# ethero_v1.net
KiCad netlist of a schematic drawn in EAGLE
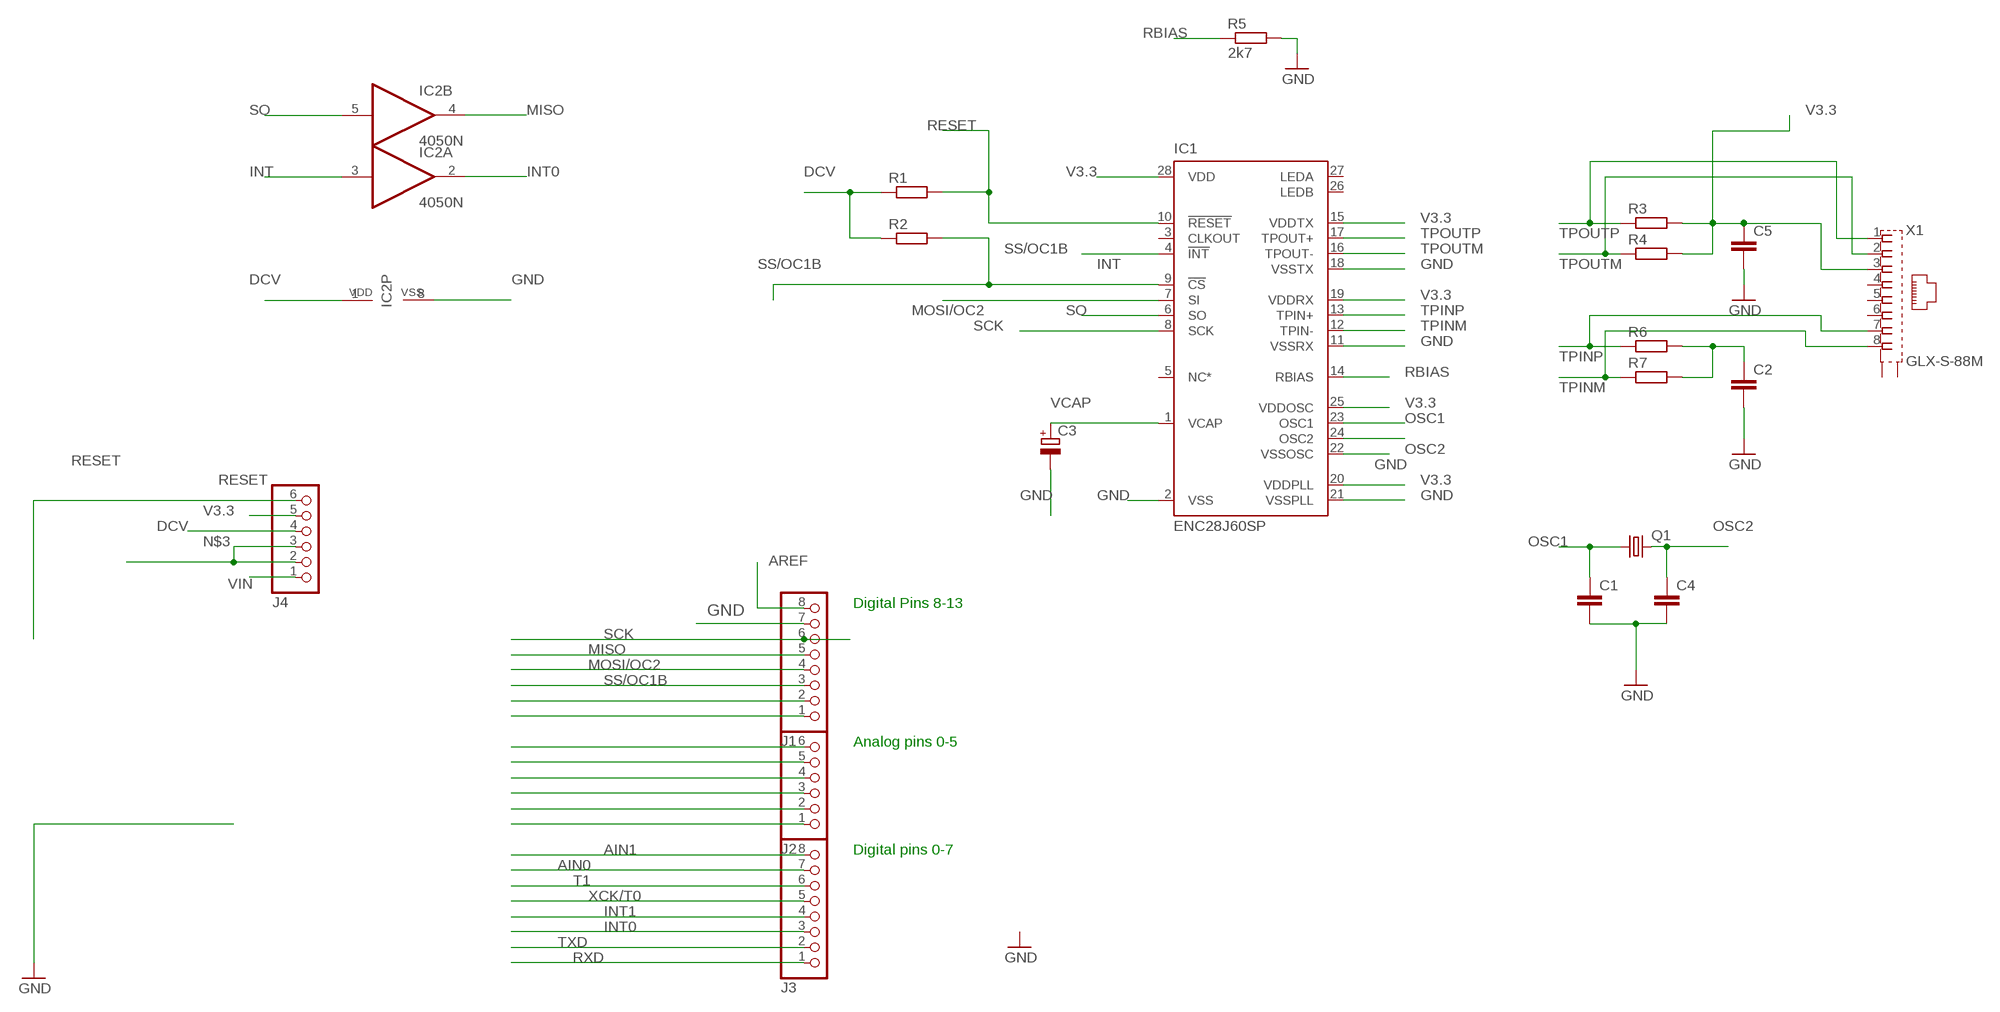
[diagram p0: schematic, sheet 1]

(export (version "E")
  (design (tool "Eeschema 10.0.6"))
  (components
    (comp (ref "C1")
      (value "C-EU025-025X050")
      (footprint "eagle-import:C025-025X050")
      (libsource (lib "eagle-import") (part "C-EU025-025X050"))
    )
    (comp (ref "C2")
      (value "C-EU025-025X050")
      (footprint "eagle-import:C025-025X050")
      (libsource (lib "eagle-import") (part "C-EU025-025X050"))
    )
    (comp (ref "C3")
      (value "CPOL-EUE5-5")
      (footprint "eagle-import:E5-5")
      (libsource (lib "eagle-import") (part "CPOL-EUE5-5"))
    )
    (comp (ref "C4")
      (value "C-EU025-025X050")
      (footprint "eagle-import:C025-025X050")
      (libsource (lib "eagle-import") (part "C-EU025-025X050"))
    )
    (comp (ref "C5")
      (value "C-EU025-025X050")
      (footprint "eagle-import:C025-025X050")
      (libsource (lib "eagle-import") (part "C-EU025-025X050"))
    )
    (comp (ref "IC1")
      (value "ENC28J60SP")
      (footprint "eagle-import:DIL28-3")
      (fields (field (name "MF") "MICROCHIP") (field (name "MPN") "ENC28J60/SP"))
      (libsource (lib "eagle-import") (part "ENC28J60SP"))
    )
    (comp (ref "IC2")
      (value "4050N")
      (footprint "eagle-import:DIL16")
      (libsource (lib "eagle-import") (part "4050N"))
    )
    (comp (ref "J1")
      (value "PINHD-1X8")
      (footprint "eagle-import:1X08")
      (libsource (lib "eagle-import") (part "PINHD-1X8"))
    )
    (comp (ref "J2")
      (value "PINHD-1X6")
      (footprint "eagle-import:1X06")
      (libsource (lib "eagle-import") (part "PINHD-1X6"))
    )
    (comp (ref "J3")
      (value "PINHD-1X8")
      (footprint "eagle-import:1X08")
      (libsource (lib "eagle-import") (part "PINHD-1X8"))
    )
    (comp (ref "J4")
      (value "PINHD-1X6")
      (footprint "eagle-import:1X06")
      (libsource (lib "eagle-import") (part "PINHD-1X6"))
    )
    (comp (ref "Q1")
      (value "CRYSTALHC18U-V")
      (footprint "eagle-import:HC18U-V")
      (libsource (lib "eagle-import") (part "CRYSTALHC18U-V"))
    )
    (comp (ref "R1")
      (value "R-EU_0204/7")
      (footprint "eagle-import:0204_7")
      (libsource (lib "eagle-import") (part "R-EU_0204/7"))
    )
    (comp (ref "R2")
      (value "R-EU_0204/7")
      (footprint "eagle-import:0204_7")
      (libsource (lib "eagle-import") (part "R-EU_0204/7"))
    )
    (comp (ref "R3")
      (value "R-EU_0204/7")
      (footprint "eagle-import:0204_7")
      (libsource (lib "eagle-import") (part "R-EU_0204/7"))
    )
    (comp (ref "R4")
      (value "R-EU_0204/7")
      (footprint "eagle-import:0204_7")
      (libsource (lib "eagle-import") (part "R-EU_0204/7"))
    )
    (comp (ref "R5")
      (value "2k7")
      (footprint "eagle-import:0204_7")
      (libsource (lib "eagle-import") (part "R-EU_0204/7"))
    )
    (comp (ref "R6")
      (value "R-EU_0204/7")
      (footprint "eagle-import:0204_7")
      (libsource (lib "eagle-import") (part "R-EU_0204/7"))
    )
    (comp (ref "R7")
      (value "R-EU_0204/7")
      (footprint "eagle-import:0204_7")
      (libsource (lib "eagle-import") (part "R-EU_0204/7"))
    )
    (comp (ref "X1")
      (value "GLX-S-88M")
      (footprint "eagle-import:GLX-S-88M")
      (libsource (lib "eagle-import") (part "GLX-S-88M"))
    )
  )
  (nets
    (net (code "1") (name "/AIN0") (class "Default")
      (node (ref "J3") (pin "7") (pinfunction "7_7") (pintype "passive"))
    )
    (net (code "2") (name "/AIN1") (class "Default")
      (node (ref "J3") (pin "8") (pinfunction "8_8") (pintype "passive"))
    )
    (net (code "3") (name "/AREF") (class "Default")
      (node (ref "J1") (pin "8") (pinfunction "8_8") (pintype "passive"))
    )
    (net (code "4") (name "/DCV") (class "Default")
      (node (ref "IC2") (pin "1") (pinfunction "VDD_1") (pintype "power_in"))
      (node (ref "J4") (pin "4") (pinfunction "4_4") (pintype "passive"))
      (node (ref "R1") (pin "1") (pinfunction "1_1") (pintype "passive"))
      (node (ref "R2") (pin "1") (pinfunction "1_1") (pintype "passive"))
    )
    (net (code "5") (name "/INT") (class "Default")
      (node (ref "IC1") (pin "4") (pinfunction "~{INT}_4") (pintype "output"))
      (node (ref "IC2") (pin "3") (pinfunction "I_3") (pintype "input"))
    )
    (net (code "6") (name "/INT0") (class "Default")
      (node (ref "IC2") (pin "2") (pinfunction "O_2") (pintype "output"))
      (node (ref "J3") (pin "3") (pinfunction "3_3") (pintype "passive"))
    )
    (net (code "7") (name "/INT1") (class "Default")
      (node (ref "J3") (pin "4") (pinfunction "4_4") (pintype "passive"))
    )
    (net (code "8") (name "/MISO") (class "Default")
      (node (ref "IC2") (pin "4") (pinfunction "O_4") (pintype "output"))
      (node (ref "J1") (pin "5") (pinfunction "5_5") (pintype "passive"))
    )
    (net (code "9") (name "/MOSI{slash}OC2") (class "Default")
      (node (ref "IC1") (pin "7") (pinfunction "SI_7") (pintype "input"))
      (node (ref "J1") (pin "4") (pinfunction "4_4") (pintype "passive"))
    )
    (net (code "10") (name "/N$3") (class "Default")
      (node (ref "J4") (pin "2") (pinfunction "2_2") (pintype "passive"))
      (node (ref "J4") (pin "3") (pinfunction "3_3") (pintype "passive"))
    )
    (net (code "11") (name "/OSC1") (class "Default")
      (node (ref "C1") (pin "1") (pinfunction "1_1") (pintype "passive"))
      (node (ref "IC1") (pin "23") (pinfunction "OSC1_23") (pintype "input"))
      (node (ref "Q1") (pin "1") (pinfunction "1_1") (pintype "passive"))
    )
    (net (code "12") (name "/OSC2") (class "Default")
      (node (ref "C4") (pin "1") (pinfunction "1_1") (pintype "passive"))
      (node (ref "IC1") (pin "24") (pinfunction "OSC2_24") (pintype "output"))
      (node (ref "Q1") (pin "2") (pinfunction "2_2") (pintype "passive"))
    )
    (net (code "13") (name "/RBIAS") (class "Default")
      (node (ref "IC1") (pin "14") (pinfunction "RBIAS_14") (pintype "input"))
      (node (ref "R5") (pin "1") (pinfunction "1_1") (pintype "passive"))
    )
    (net (code "14") (name "/RESET") (class "Default")
      (node (ref "IC1") (pin "10") (pinfunction "~{RESET}_10") (pintype "input"))
      (node (ref "J4") (pin "6") (pinfunction "6_6") (pintype "passive"))
      (node (ref "R1") (pin "2") (pinfunction "2_2") (pintype "passive"))
    )
    (net (code "15") (name "/RXD") (class "Default")
      (node (ref "J3") (pin "1") (pinfunction "1_1") (pintype "passive"))
    )
    (net (code "16") (name "/SCK") (class "Default")
      (node (ref "IC1") (pin "8") (pinfunction "SCK_8") (pintype "input"))
      (node (ref "J1") (pin "6") (pinfunction "6_6") (pintype "passive"))
    )
    (net (code "17") (name "/SO") (class "Default")
      (node (ref "IC1") (pin "6") (pinfunction "SO_6") (pintype "output"))
      (node (ref "IC2") (pin "5") (pinfunction "I_5") (pintype "input"))
    )
    (net (code "18") (name "/SS{slash}OC1B") (class "Default")
      (node (ref "IC1") (pin "9") (pinfunction "~{CS}_9") (pintype "input"))
      (node (ref "J1") (pin "3") (pinfunction "3_3") (pintype "passive"))
      (node (ref "R2") (pin "2") (pinfunction "2_2") (pintype "passive"))
    )
    (net (code "19") (name "/T1") (class "Default")
      (node (ref "J3") (pin "6") (pinfunction "6_6") (pintype "passive"))
    )
    (net (code "20") (name "/TPINM") (class "Default")
      (node (ref "IC1") (pin "12") (pinfunction "TPIN-_12") (pintype "input"))
      (node (ref "R7") (pin "1") (pinfunction "1_1") (pintype "passive"))
      (node (ref "X1") (pin "8") (pinfunction "8_8") (pintype "passive"))
    )
    (net (code "21") (name "/TPINP") (class "Default")
      (node (ref "IC1") (pin "13") (pinfunction "TPIN+_13") (pintype "input"))
      (node (ref "R6") (pin "1") (pinfunction "1_1") (pintype "passive"))
      (node (ref "X1") (pin "7") (pinfunction "7_7") (pintype "passive"))
    )
    (net (code "22") (name "/TPOUTM") (class "Default")
      (node (ref "IC1") (pin "16") (pinfunction "TPOUT-_16") (pintype "output"))
      (node (ref "R4") (pin "1") (pinfunction "1_1") (pintype "passive"))
      (node (ref "X1") (pin "2") (pinfunction "2_2") (pintype "passive"))
    )
    (net (code "23") (name "/TPOUTP") (class "Default")
      (node (ref "IC1") (pin "17") (pinfunction "TPOUT+_17") (pintype "output"))
      (node (ref "R3") (pin "1") (pinfunction "1_1") (pintype "passive"))
      (node (ref "X1") (pin "1") (pinfunction "1_1") (pintype "passive"))
    )
    (net (code "24") (name "/TXD") (class "Default")
      (node (ref "J3") (pin "2") (pinfunction "2_2") (pintype "passive"))
    )
    (net (code "25") (name "/V3.3") (class "Default")
      (node (ref "C5") (pin "1") (pinfunction "1_1") (pintype "passive"))
      (node (ref "IC1") (pin "15") (pinfunction "VDDTX_15") (pintype "input"))
      (node (ref "IC1") (pin "19") (pinfunction "VDDRX_19") (pintype "input"))
      (node (ref "IC1") (pin "20") (pinfunction "VDDPLL_20") (pintype "input"))
      (node (ref "IC1") (pin "25") (pinfunction "VDDOSC_25") (pintype "input"))
      (node (ref "IC1") (pin "28") (pinfunction "VDD_28") (pintype "input"))
      (node (ref "J4") (pin "5") (pinfunction "5_5") (pintype "passive"))
      (node (ref "R3") (pin "2") (pinfunction "2_2") (pintype "passive"))
      (node (ref "R4") (pin "2") (pinfunction "2_2") (pintype "passive"))
      (node (ref "X1") (pin "3") (pinfunction "3_3") (pintype "passive"))
    )
    (net (code "26") (name "/VCAP") (class "Default")
      (node (ref "C3") (pin "+") (pinfunction "+_+") (pintype "passive"))
      (node (ref "IC1") (pin "1") (pinfunction "VCAP_1") (pintype "input"))
    )
    (net (code "27") (name "/VIN") (class "Default")
      (node (ref "J4") (pin "1") (pinfunction "1_1") (pintype "passive"))
    )
    (net (code "28") (name "/XCK{slash}T0") (class "Default")
      (node (ref "J3") (pin "5") (pinfunction "5_5") (pintype "passive"))
    )
    (net (code "29") (name "GND") (class "Default")
      (node (ref "C1") (pin "2") (pinfunction "2_2") (pintype "passive"))
      (node (ref "C2") (pin "2") (pinfunction "2_2") (pintype "passive"))
      (node (ref "C3") (pin "-") (pinfunction "-_-") (pintype "passive"))
      (node (ref "C4") (pin "2") (pinfunction "2_2") (pintype "passive"))
      (node (ref "C5") (pin "2") (pinfunction "2_2") (pintype "passive"))
      (node (ref "IC1") (pin "11") (pinfunction "VSSRX_11") (pintype "input"))
      (node (ref "IC1") (pin "18") (pinfunction "VSSTX_18") (pintype "input"))
      (node (ref "IC1") (pin "2") (pinfunction "VSS_2") (pintype "input"))
      (node (ref "IC1") (pin "21") (pinfunction "VSSPLL_21") (pintype "input"))
      (node (ref "IC1") (pin "22") (pinfunction "VSSOSC_22") (pintype "input"))
      (node (ref "IC2") (pin "8") (pinfunction "VSS_8") (pintype "power_in"))
      (node (ref "J1") (pin "7") (pinfunction "7_7") (pintype "passive"))
      (node (ref "R5") (pin "2") (pinfunction "2_2") (pintype "passive"))
    )
    (net (code "30") (name "Net-(C2-Pad1)") (class "Default")
      (node (ref "C2") (pin "1") (pinfunction "1_1") (pintype "passive"))
      (node (ref "R6") (pin "2") (pinfunction "2_2") (pintype "passive"))
      (node (ref "R7") (pin "2") (pinfunction "2_2") (pintype "passive"))
    )
    (net (code "31") (name "unconnected-(IC1-CLKOUT-Pad3)") (class "Default")
      (node (ref "IC1") (pin "3") (pinfunction "CLKOUT_3") (pintype "output"))
    )
    (net (code "32") (name "unconnected-(IC1-LEDA-Pad27)") (class "Default")
      (node (ref "IC1") (pin "27") (pinfunction "LEDA_27") (pintype "output"))
    )
    (net (code "33") (name "unconnected-(IC1-LEDB-Pad26)") (class "Default")
      (node (ref "IC1") (pin "26") (pinfunction "LEDB_26") (pintype "output"))
    )
    (net (code "34") (name "unconnected-(IC1-NC*-Pad5)") (class "Default")
      (node (ref "IC1") (pin "5") (pinfunction "NC*_5") (pintype "output"))
    )
    (net (code "35") (name "unconnected-(J1-Pad1)") (class "Default")
      (node (ref "J1") (pin "1") (pinfunction "1_1") (pintype "passive"))
    )
    (net (code "36") (name "unconnected-(J1-Pad2)") (class "Default")
      (node (ref "J1") (pin "2") (pinfunction "2_2") (pintype "passive"))
    )
    (net (code "37") (name "unconnected-(J2-Pad1)") (class "Default")
      (node (ref "J2") (pin "1") (pinfunction "1_1") (pintype "passive"))
    )
    (net (code "38") (name "unconnected-(J2-Pad2)") (class "Default")
      (node (ref "J2") (pin "2") (pinfunction "2_2") (pintype "passive"))
    )
    (net (code "39") (name "unconnected-(J2-Pad3)") (class "Default")
      (node (ref "J2") (pin "3") (pinfunction "3_3") (pintype "passive"))
    )
    (net (code "40") (name "unconnected-(J2-Pad4)") (class "Default")
      (node (ref "J2") (pin "4") (pinfunction "4_4") (pintype "passive"))
    )
    (net (code "41") (name "unconnected-(J2-Pad5)") (class "Default")
      (node (ref "J2") (pin "5") (pinfunction "5_5") (pintype "passive"))
    )
    (net (code "42") (name "unconnected-(J2-Pad6)") (class "Default")
      (node (ref "J2") (pin "6") (pinfunction "6_6") (pintype "passive"))
    )
    (net (code "43") (name "unconnected-(X1-Pad4)") (class "Default")
      (node (ref "X1") (pin "4") (pinfunction "4_4") (pintype "passive"))
    )
    (net (code "44") (name "unconnected-(X1-Pad5)") (class "Default")
      (node (ref "X1") (pin "5") (pinfunction "5_5") (pintype "passive"))
    )
    (net (code "45") (name "unconnected-(X1-Pad6)") (class "Default")
      (node (ref "X1") (pin "6") (pinfunction "6_6") (pintype "passive"))
    )
    (net (code "46") (name "unconnected-(X1-PadS1)") (class "Default")
      (node (ref "X1") (pin "S1") (pinfunction "S1_S1") (pintype "passive"))
    )
    (net (code "47") (name "unconnected-(X1-PadS2)") (class "Default")
      (node (ref "X1") (pin "S2") (pinfunction "S2_S2") (pintype "passive"))
    )
  )
)
